# RFID_ver_1_1.net
KiCad netlist of a schematic drawn in EAGLE
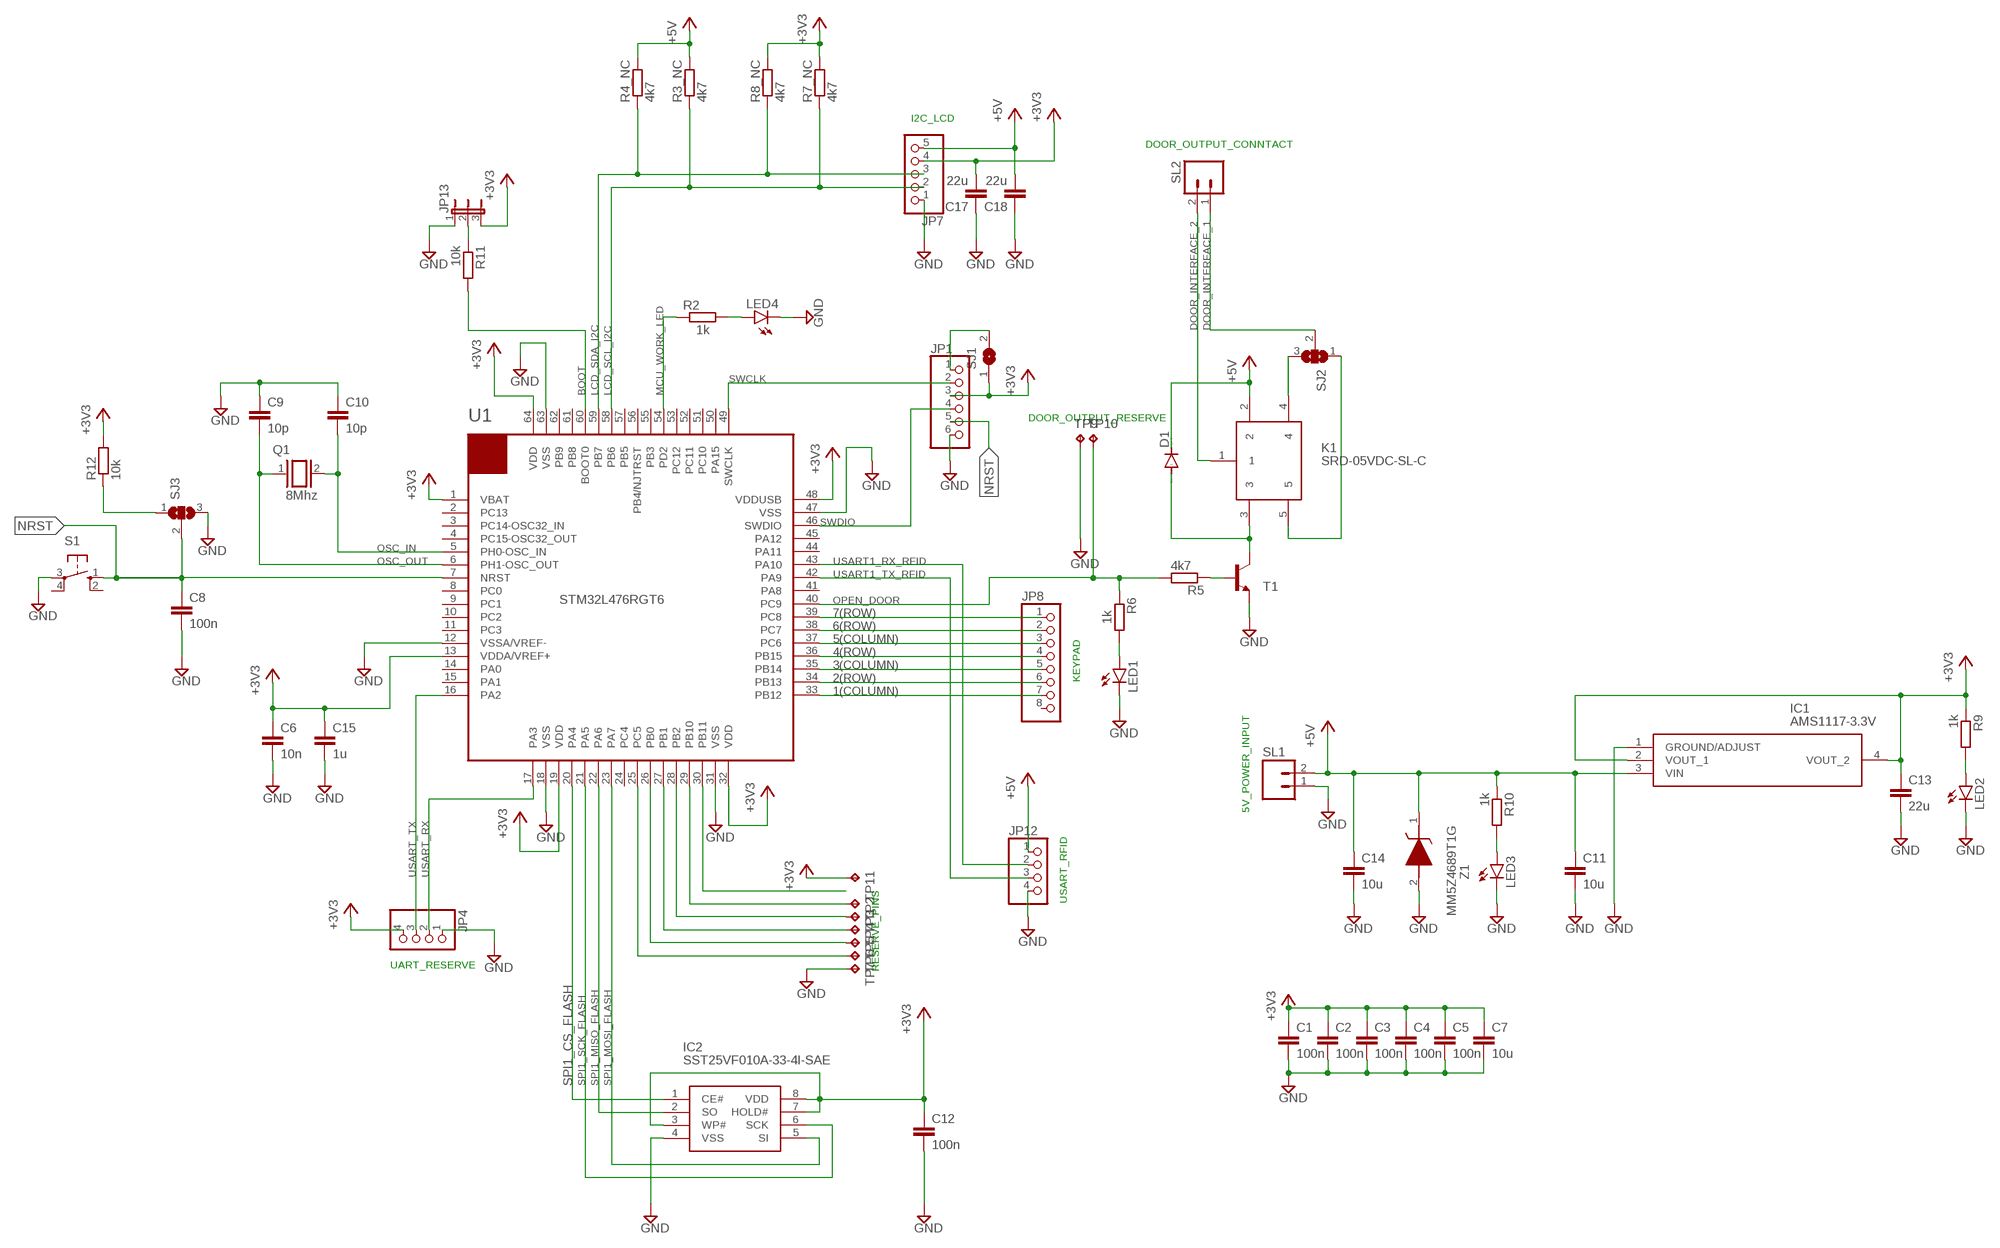
[diagram p0: schematic, sheet 1]

(export (version "E")
  (design (tool "Eeschema 10.0.6"))
  (components
    (comp (ref "C1")
      (value "100n")
      (footprint "eagle-import:C0805")
      (libsource (lib "eagle-import") (part "C-EUC0805"))
    )
    (comp (ref "C2")
      (value "100n")
      (footprint "eagle-import:C0805")
      (libsource (lib "eagle-import") (part "C-EUC0805"))
    )
    (comp (ref "C3")
      (value "100n")
      (footprint "eagle-import:C0805")
      (libsource (lib "eagle-import") (part "C-EUC0805"))
    )
    (comp (ref "C4")
      (value "100n")
      (footprint "eagle-import:C0805")
      (libsource (lib "eagle-import") (part "C-EUC0805"))
    )
    (comp (ref "C5")
      (value "100n")
      (footprint "eagle-import:C0805")
      (libsource (lib "eagle-import") (part "C-EUC0805"))
    )
    (comp (ref "C6")
      (value "10n")
      (footprint "eagle-import:C0805")
      (libsource (lib "eagle-import") (part "C-EUC0805"))
    )
    (comp (ref "C7")
      (value "10u")
      (footprint "eagle-import:C0805")
      (libsource (lib "eagle-import") (part "C-EUC0805"))
    )
    (comp (ref "C8")
      (value "100n")
      (footprint "eagle-import:C0805")
      (libsource (lib "eagle-import") (part "C-EUC0805"))
    )
    (comp (ref "C9")
      (value "10p")
      (footprint "eagle-import:C0805")
      (libsource (lib "eagle-import") (part "C-EUC0805"))
    )
    (comp (ref "C10")
      (value "10p")
      (footprint "eagle-import:C0805")
      (libsource (lib "eagle-import") (part "C-EUC0805"))
    )
    (comp (ref "C11")
      (value "10u")
      (footprint "eagle-import:C0805")
      (libsource (lib "eagle-import") (part "C-EUC0805"))
    )
    (comp (ref "C12")
      (value "100n")
      (footprint "eagle-import:C0805")
      (libsource (lib "eagle-import") (part "C-EUC0805"))
    )
    (comp (ref "C13")
      (value "22u")
      (footprint "eagle-import:C0805")
      (libsource (lib "eagle-import") (part "C-EUC0805"))
    )
    (comp (ref "C14")
      (value "10u")
      (footprint "eagle-import:C0805")
      (libsource (lib "eagle-import") (part "C-EUC0805"))
    )
    (comp (ref "C15")
      (value "1u")
      (footprint "eagle-import:C0805")
      (libsource (lib "eagle-import") (part "C-EUC0805"))
    )
    (comp (ref "C17")
      (value "22u")
      (footprint "eagle-import:C0805")
      (libsource (lib "eagle-import") (part "C-EUC0805"))
    )
    (comp (ref "C18")
      (value "22u")
      (footprint "eagle-import:C0805")
      (libsource (lib "eagle-import") (part "C-EUC0805"))
    )
    (comp (ref "D1")
      (value "DIODE-DO-214AC")
      (footprint "eagle-import:DO-214AC")
      (libsource (lib "eagle-import") (part "DIODE-DO-214AC"))
    )
    (comp (ref "IC1")
      (value "AMS1117-3.3V")
      (footprint "eagle-import:SOT229P700X180-4N")
      (fields (field (name "MANUFACTURER_PART_NUMBER") "ams1117-3.3v"))
      (libsource (lib "eagle-import") (part "AMS1117-3.3V"))
    )
    (comp (ref "IC2")
      (value "SST25VF010A-33-4I-SAE")
      (footprint "eagle-import:SOIC127P600X175-8N")
      (fields (field (name "MOUSER_PART_NUMBER") "804-25VF010A3ISAE"))
      (libsource (lib "eagle-import") (part "SST25VF010A-33-4I-SAE"))
    )
    (comp (ref "JP1")
      (value "PINHD-1X6")
      (footprint "eagle-import:1X06")
      (libsource (lib "eagle-import") (part "PINHD-1X6"))
    )
    (comp (ref "JP4")
      (value "PINHD-1X4")
      (footprint "eagle-import:1X04")
      (libsource (lib "eagle-import") (part "PINHD-1X4"))
    )
    (comp (ref "JP7")
      (value "PINHD-1X5")
      (footprint "eagle-import:1X05")
      (libsource (lib "eagle-import") (part "PINHD-1X5"))
    )
    (comp (ref "JP8")
      (value "PINHD-1X8")
      (footprint "eagle-import:1X08")
      (libsource (lib "eagle-import") (part "PINHD-1X8"))
    )
    (comp (ref "JP12")
      (value "PINHD-1X4")
      (footprint "eagle-import:1X04")
      (libsource (lib "eagle-import") (part "PINHD-1X4"))
    )
    (comp (ref "JP13")
      (value "JP2E")
      (footprint "eagle-import:JP2")
      (libsource (lib "eagle-import") (part "JP2E"))
    )
    (comp (ref "K1")
      (value "SRD-05VDC-SL-C")
      (footprint "eagle-import:SRD")
      (libsource (lib "eagle-import") (part "SRD-05VDC-SL-C"))
    )
    (comp (ref "LED1")
      (value "LEDCHIP-LED0805")
      (footprint "eagle-import:CHIP-LED0805")
      (libsource (lib "eagle-import") (part "LEDCHIP-LED0805"))
    )
    (comp (ref "LED2")
      (value "LEDCHIP-LED0805")
      (footprint "eagle-import:CHIP-LED0805")
      (libsource (lib "eagle-import") (part "LEDCHIP-LED0805"))
    )
    (comp (ref "LED3")
      (value "LEDCHIP-LED0805")
      (footprint "eagle-import:CHIP-LED0805")
      (libsource (lib "eagle-import") (part "LEDCHIP-LED0805"))
    )
    (comp (ref "LED4")
      (value "LEDCHIP-LED0805")
      (footprint "eagle-import:CHIP-LED0805")
      (libsource (lib "eagle-import") (part "LEDCHIP-LED0805"))
    )
    (comp (ref "Q1")
      (value "8Mhz")
      (footprint "eagle-import:QS")
      (libsource (lib "eagle-import") (part "XTAL/S"))
    )
    (comp (ref "R2")
      (value "1k")
      (footprint "eagle-import:R0805")
      (libsource (lib "eagle-import") (part "R-EU_R0805"))
    )
    (comp (ref "R3_NC")
      (value "4k7")
      (footprint "eagle-import:R0805")
      (libsource (lib "eagle-import") (part "R-EU_R0805"))
    )
    (comp (ref "R4_NC")
      (value "4k7")
      (footprint "eagle-import:R0805")
      (libsource (lib "eagle-import") (part "R-EU_R0805"))
    )
    (comp (ref "R5")
      (value "4k7")
      (footprint "eagle-import:R0805")
      (libsource (lib "eagle-import") (part "R-EU_R0805"))
    )
    (comp (ref "R6")
      (value "1k")
      (footprint "eagle-import:R0805")
      (libsource (lib "eagle-import") (part "R-EU_R0805"))
    )
    (comp (ref "R7_NC")
      (value "4k7")
      (footprint "eagle-import:R0805")
      (libsource (lib "eagle-import") (part "R-EU_R0805"))
    )
    (comp (ref "R8_NC")
      (value "4k7")
      (footprint "eagle-import:R0805")
      (libsource (lib "eagle-import") (part "R-EU_R0805"))
    )
    (comp (ref "R9")
      (value "1k")
      (footprint "eagle-import:R0805")
      (libsource (lib "eagle-import") (part "R-EU_R0805"))
    )
    (comp (ref "R10")
      (value "1k")
      (footprint "eagle-import:R0805")
      (libsource (lib "eagle-import") (part "R-EU_R0805"))
    )
    (comp (ref "R11")
      (value "10k")
      (footprint "eagle-import:R0805")
      (libsource (lib "eagle-import") (part "R-EU_R0805"))
    )
    (comp (ref "R12")
      (value "10k")
      (footprint "eagle-import:R0805")
      (libsource (lib "eagle-import") (part "R-EU_R0805"))
    )
    (comp (ref "S1")
      (value "10-XX")
      (footprint "eagle-import:B3F-10XX")
      (fields (field (name "MPN") "B3F-1000"))
      (libsource (lib "eagle-import") (part "10-XX"))
    )
    (comp (ref "SJ1") (value "SJ") (footprint "eagle-import:SJ") (libsource (lib "eagle-import") (part "SJ")))
    (comp (ref "SJ2")
      (value "SJ2W")
      (footprint "eagle-import:SJ_2")
      (libsource (lib "eagle-import") (part "SJ2W"))
    )
    (comp (ref "SJ3")
      (value "SJ2W")
      (footprint "eagle-import:SJ_2")
      (libsource (lib "eagle-import") (part "SJ2W"))
    )
    (comp (ref "SL1")
      (value "M02")
      (footprint "eagle-import:02P")
      (libsource (lib "eagle-import") (part "M02"))
    )
    (comp (ref "SL2")
      (value "M02")
      (footprint "eagle-import:02P")
      (libsource (lib "eagle-import") (part "M02"))
    )
    (comp (ref "T1")
      (value "BC817-NPN-SOT23-BEC")
      (footprint "eagle-import:SOT23-BEC")
      (libsource (lib "eagle-import") (part "-NPN-SOT23-BECBC817"))
    )
    (comp (ref "TP2")
      (value "TPPAD1-13")
      (footprint "eagle-import:P1-13")
      (libsource (lib "eagle-import") (part "TPPAD1-13"))
    )
    (comp (ref "TP3")
      (value "TPPAD1-13")
      (footprint "eagle-import:P1-13")
      (libsource (lib "eagle-import") (part "TPPAD1-13"))
    )
    (comp (ref "TP4")
      (value "TPPAD1-13")
      (footprint "eagle-import:P1-13")
      (libsource (lib "eagle-import") (part "TPPAD1-13"))
    )
    (comp (ref "TP5")
      (value "TPPAD1-13")
      (footprint "eagle-import:P1-13")
      (libsource (lib "eagle-import") (part "TPPAD1-13"))
    )
    (comp (ref "TP6")
      (value "TPPAD1-13")
      (footprint "eagle-import:P1-13")
      (libsource (lib "eagle-import") (part "TPPAD1-13"))
    )
    (comp (ref "TP7")
      (value "TPPAD1-13")
      (footprint "eagle-import:P1-13")
      (libsource (lib "eagle-import") (part "TPPAD1-13"))
    )
    (comp (ref "TP9")
      (value "TPPAD1-17")
      (footprint "eagle-import:P1-17")
      (libsource (lib "eagle-import") (part "TPPAD1-17"))
    )
    (comp (ref "TP10")
      (value "TPPAD1-17")
      (footprint "eagle-import:P1-17")
      (libsource (lib "eagle-import") (part "TPPAD1-17"))
    )
    (comp (ref "TP11")
      (value "TPPAD1-13")
      (footprint "eagle-import:P1-13")
      (libsource (lib "eagle-import") (part "TPPAD1-13"))
    )
    (comp (ref "U1")
      (value "STM32L476RGT6")
      (footprint "eagle-import:LQFP-64")
      (libsource (lib "eagle-import") (part "STM32L476RT6G"))
    )
    (comp (ref "Z1")
      (value "MM5Z4689T1G")
      (footprint "eagle-import:SODFL1608X70N")
      (fields (field (name "MOUSER_PART_NUMBER") "863-MM5Z4689T1G"))
      (libsource (lib "eagle-import") (part "MM5Z4689T1G"))
    )
  )
  (nets
    (net (code "1") (name "+3V3") (class "Default")
      (node (ref "C1") (pin "1") (pinfunction "1_1") (pintype "passive"))
      (node (ref "C12") (pin "1") (pinfunction "1_1") (pintype "passive"))
      (node (ref "C13") (pin "1") (pinfunction "1_1") (pintype "passive"))
      (node (ref "C15") (pin "1") (pinfunction "1_1") (pintype "passive"))
      (node (ref "C17") (pin "2") (pinfunction "2_2") (pintype "passive"))
      (node (ref "C2") (pin "1") (pinfunction "1_1") (pintype "passive"))
      (node (ref "C3") (pin "1") (pinfunction "1_1") (pintype "passive"))
      (node (ref "C4") (pin "1") (pinfunction "1_1") (pintype "passive"))
      (node (ref "C5") (pin "1") (pinfunction "1_1") (pintype "passive"))
      (node (ref "C6") (pin "1") (pinfunction "1_1") (pintype "passive"))
      (node (ref "C7") (pin "1") (pinfunction "1_1") (pintype "passive"))
      (node (ref "IC1") (pin "2") (pinfunction "VOUT_1_2") (pintype "bidirectional"))
      (node (ref "IC1") (pin "4") (pinfunction "VOUT_2_4") (pintype "bidirectional"))
      (node (ref "IC2") (pin "3") (pinfunction "WP#_3") (pintype "bidirectional"))
      (node (ref "IC2") (pin "7") (pinfunction "HOLD#_7") (pintype "bidirectional"))
      (node (ref "IC2") (pin "8") (pinfunction "VDD_8") (pintype "bidirectional"))
      (node (ref "JP1") (pin "3") (pinfunction "3_3") (pintype "passive"))
      (node (ref "JP13") (pin "3") (pinfunction "3_3") (pintype "passive"))
      (node (ref "JP4") (pin "4") (pinfunction "4_4") (pintype "passive"))
      (node (ref "JP7") (pin "4") (pinfunction "4_4") (pintype "passive"))
      (node (ref "R12") (pin "2") (pinfunction "2_2") (pintype "passive"))
      (node (ref "R7_NC") (pin "2") (pinfunction "2_2") (pintype "passive"))
      (node (ref "R8_NC") (pin "2") (pinfunction "2_2") (pintype "passive"))
      (node (ref "R9") (pin "1") (pinfunction "1_1") (pintype "passive"))
      (node (ref "SJ1") (pin "1") (pinfunction "1_1") (pintype "passive"))
      (node (ref "TP11") (pin "TP") (pinfunction "TP_TP") (pintype "input"))
      (node (ref "U1") (pin "1") (pinfunction "VBAT_1") (pintype "power_in"))
      (node (ref "U1") (pin "13") (pinfunction "VDDA/VREF+_13") (pintype "power_in"))
      (node (ref "U1") (pin "19") (pinfunction "VDD_19") (pintype "power_in"))
      (node (ref "U1") (pin "32") (pinfunction "VDD_32") (pintype "power_in"))
      (node (ref "U1") (pin "48") (pinfunction "VDDUSB_48") (pintype "power_in"))
      (node (ref "U1") (pin "64") (pinfunction "VDD_64") (pintype "power_in"))
    )
    (net (code "2") (name "+5V") (class "Default")
      (node (ref "C11") (pin "1") (pinfunction "1_1") (pintype "passive"))
      (node (ref "C14") (pin "1") (pinfunction "1_1") (pintype "passive"))
      (node (ref "C18") (pin "2") (pinfunction "2_2") (pintype "passive"))
      (node (ref "D1") (pin "C") (pinfunction "C_C") (pintype "passive"))
      (node (ref "IC1") (pin "3") (pinfunction "VIN_3") (pintype "bidirectional"))
      (node (ref "JP12") (pin "1") (pinfunction "1_1") (pintype "passive"))
      (node (ref "JP7") (pin "5") (pinfunction "5_5") (pintype "passive"))
      (node (ref "K1") (pin "2") (pinfunction "2_2") (pintype "bidirectional"))
      (node (ref "R10") (pin "1") (pinfunction "1_1") (pintype "passive"))
      (node (ref "R3_NC") (pin "2") (pinfunction "2_2") (pintype "passive"))
      (node (ref "R4_NC") (pin "2") (pinfunction "2_2") (pintype "passive"))
      (node (ref "SL1") (pin "2") (pinfunction "2_2") (pintype "passive"))
      (node (ref "Z1") (pin "1") (pinfunction "K_1") (pintype "bidirectional"))
    )
    (net (code "3") (name "/1(COLUMN)") (class "Default")
      (node (ref "JP8") (pin "7") (pinfunction "7_7") (pintype "passive"))
      (node (ref "U1") (pin "33") (pinfunction "PB12_33") (pintype "bidirectional"))
    )
    (net (code "4") (name "/2(ROW)") (class "Default")
      (node (ref "JP8") (pin "6") (pinfunction "6_6") (pintype "passive"))
      (node (ref "U1") (pin "34") (pinfunction "PB13_34") (pintype "bidirectional"))
    )
    (net (code "5") (name "/3(COLUMN)") (class "Default")
      (node (ref "JP8") (pin "5") (pinfunction "5_5") (pintype "passive"))
      (node (ref "U1") (pin "35") (pinfunction "PB14_35") (pintype "bidirectional"))
    )
    (net (code "6") (name "/4(ROW)") (class "Default")
      (node (ref "JP8") (pin "4") (pinfunction "4_4") (pintype "passive"))
      (node (ref "U1") (pin "36") (pinfunction "PB15_36") (pintype "bidirectional"))
    )
    (net (code "7") (name "/5(COLUMN)") (class "Default")
      (node (ref "JP8") (pin "3") (pinfunction "3_3") (pintype "passive"))
      (node (ref "U1") (pin "37") (pinfunction "PC6_37") (pintype "bidirectional"))
    )
    (net (code "8") (name "/6(ROW)") (class "Default")
      (node (ref "JP8") (pin "2") (pinfunction "2_2") (pintype "passive"))
      (node (ref "U1") (pin "38") (pinfunction "PC7_38") (pintype "bidirectional"))
    )
    (net (code "9") (name "/7(ROW)") (class "Default")
      (node (ref "JP8") (pin "1") (pinfunction "1_1") (pintype "passive"))
      (node (ref "U1") (pin "39") (pinfunction "PC8_39") (pintype "bidirectional"))
    )
    (net (code "10") (name "/BOOT") (class "Default")
      (node (ref "R11") (pin "2") (pinfunction "2_2") (pintype "passive"))
      (node (ref "U1") (pin "60") (pinfunction "BOOT0_60") (pintype "input"))
    )
    (net (code "11") (name "/DOOR_INTERFACE_1") (class "Default")
      (node (ref "SJ2") (pin "2") (pinfunction "2_2") (pintype "passive"))
      (node (ref "SL2") (pin "1") (pinfunction "1_1") (pintype "passive"))
    )
    (net (code "12") (name "/DOOR_INTERFACE_2") (class "Default")
      (node (ref "K1") (pin "1") (pinfunction "1_1") (pintype "bidirectional"))
      (node (ref "SL2") (pin "2") (pinfunction "2_2") (pintype "passive"))
    )
    (net (code "13") (name "/LCD_SCL_I2C") (class "Default")
      (node (ref "JP7") (pin "2") (pinfunction "2_2") (pintype "passive"))
      (node (ref "R3_NC") (pin "1") (pinfunction "1_1") (pintype "passive"))
      (node (ref "R7_NC") (pin "1") (pinfunction "1_1") (pintype "passive"))
      (node (ref "U1") (pin "58") (pinfunction "PB6_58") (pintype "bidirectional"))
    )
    (net (code "14") (name "/LCD_SDA_I2C") (class "Default")
      (node (ref "JP7") (pin "3") (pinfunction "3_3") (pintype "passive"))
      (node (ref "R4_NC") (pin "1") (pinfunction "1_1") (pintype "passive"))
      (node (ref "R8_NC") (pin "1") (pinfunction "1_1") (pintype "passive"))
      (node (ref "U1") (pin "59") (pinfunction "PB7_59") (pintype "bidirectional"))
    )
    (net (code "15") (name "/MCU_WORK_LED") (class "Default")
      (node (ref "R2") (pin "1") (pinfunction "1_1") (pintype "passive"))
      (node (ref "U1") (pin "54") (pinfunction "PD2_54") (pintype "bidirectional"))
    )
    (net (code "16") (name "/OPEN_DOOR") (class "Default")
      (node (ref "R5") (pin "2") (pinfunction "2_2") (pintype "passive"))
      (node (ref "R6") (pin "1") (pinfunction "1_1") (pintype "passive"))
      (node (ref "TP10") (pin "TP") (pinfunction "TP_TP") (pintype "input"))
      (node (ref "U1") (pin "40") (pinfunction "PC9_40") (pintype "bidirectional"))
    )
    (net (code "17") (name "/OSC_IN") (class "Default")
      (node (ref "C10") (pin "2") (pinfunction "2_2") (pintype "passive"))
      (node (ref "Q1") (pin "2") (pinfunction "2_2") (pintype "passive"))
      (node (ref "U1") (pin "5") (pinfunction "PH0-OSC_IN_5") (pintype "bidirectional"))
    )
    (net (code "18") (name "/OSC_OUT") (class "Default")
      (node (ref "C9") (pin "2") (pinfunction "2_2") (pintype "passive"))
      (node (ref "Q1") (pin "1") (pinfunction "1_1") (pintype "passive"))
      (node (ref "U1") (pin "6") (pinfunction "PH1-OSC_OUT_6") (pintype "bidirectional"))
    )
    (net (code "19") (name "/SPI1_CS_FLASH") (class "Default")
      (node (ref "IC2") (pin "1") (pinfunction "CE#_1") (pintype "bidirectional"))
      (node (ref "U1") (pin "20") (pinfunction "PA4_20") (pintype "bidirectional"))
    )
    (net (code "20") (name "/SPI1_MISO_FLASH") (class "Default")
      (node (ref "IC2") (pin "2") (pinfunction "SO_2") (pintype "bidirectional"))
      (node (ref "U1") (pin "22") (pinfunction "PA6_22") (pintype "bidirectional"))
    )
    (net (code "21") (name "/SPI1_MOSI_FLASH") (class "Default")
      (node (ref "IC2") (pin "5") (pinfunction "SI_5") (pintype "bidirectional"))
      (node (ref "U1") (pin "23") (pinfunction "PA7_23") (pintype "bidirectional"))
    )
    (net (code "22") (name "/SPI1_SCK_FLASH") (class "Default")
      (node (ref "IC2") (pin "6") (pinfunction "SCK_6") (pintype "bidirectional"))
      (node (ref "U1") (pin "21") (pinfunction "PA5_21") (pintype "bidirectional"))
    )
    (net (code "23") (name "/SWCLK") (class "Default")
      (node (ref "JP1") (pin "2") (pinfunction "2_2") (pintype "passive"))
      (node (ref "U1") (pin "49") (pinfunction "SWCLK_49") (pintype "bidirectional"))
    )
    (net (code "24") (name "/SWDIO") (class "Default")
      (node (ref "JP1") (pin "4") (pinfunction "4_4") (pintype "passive"))
      (node (ref "U1") (pin "46") (pinfunction "SWDIO_46") (pintype "bidirectional"))
    )
    (net (code "25") (name "/USART1_RX_RFID") (class "Default")
      (node (ref "JP12") (pin "2") (pinfunction "2_2") (pintype "passive"))
      (node (ref "U1") (pin "43") (pinfunction "PA10_43") (pintype "bidirectional"))
    )
    (net (code "26") (name "/USART1_TX_RFID") (class "Default")
      (node (ref "JP12") (pin "3") (pinfunction "3_3") (pintype "passive"))
      (node (ref "U1") (pin "42") (pinfunction "PA9_42") (pintype "bidirectional"))
    )
    (net (code "27") (name "/USART_RX") (class "Default")
      (node (ref "JP4") (pin "2") (pinfunction "2_2") (pintype "passive"))
      (node (ref "U1") (pin "17") (pinfunction "PA3_17") (pintype "bidirectional"))
    )
    (net (code "28") (name "/USART_TX") (class "Default")
      (node (ref "JP4") (pin "3") (pinfunction "3_3") (pintype "passive"))
      (node (ref "U1") (pin "16") (pinfunction "PA2_16") (pintype "bidirectional"))
    )
    (net (code "29") (name "GND") (class "Default")
      (node (ref "C1") (pin "2") (pinfunction "2_2") (pintype "passive"))
      (node (ref "C10") (pin "1") (pinfunction "1_1") (pintype "passive"))
      (node (ref "C11") (pin "2") (pinfunction "2_2") (pintype "passive"))
      (node (ref "C12") (pin "2") (pinfunction "2_2") (pintype "passive"))
      (node (ref "C13") (pin "2") (pinfunction "2_2") (pintype "passive"))
      (node (ref "C14") (pin "2") (pinfunction "2_2") (pintype "passive"))
      (node (ref "C15") (pin "2") (pinfunction "2_2") (pintype "passive"))
      (node (ref "C17") (pin "1") (pinfunction "1_1") (pintype "passive"))
      (node (ref "C18") (pin "1") (pinfunction "1_1") (pintype "passive"))
      (node (ref "C2") (pin "2") (pinfunction "2_2") (pintype "passive"))
      (node (ref "C3") (pin "2") (pinfunction "2_2") (pintype "passive"))
      (node (ref "C4") (pin "2") (pinfunction "2_2") (pintype "passive"))
      (node (ref "C5") (pin "2") (pinfunction "2_2") (pintype "passive"))
      (node (ref "C6") (pin "2") (pinfunction "2_2") (pintype "passive"))
      (node (ref "C7") (pin "2") (pinfunction "2_2") (pintype "passive"))
      (node (ref "C8") (pin "2") (pinfunction "2_2") (pintype "passive"))
      (node (ref "C9") (pin "1") (pinfunction "1_1") (pintype "passive"))
      (node (ref "IC1") (pin "1") (pinfunction "GROUND/ADJUST_1") (pintype "bidirectional"))
      (node (ref "IC2") (pin "4") (pinfunction "VSS_4") (pintype "bidirectional"))
      (node (ref "JP1") (pin "6") (pinfunction "6_6") (pintype "passive"))
      (node (ref "JP12") (pin "4") (pinfunction "4_4") (pintype "passive"))
      (node (ref "JP13") (pin "1") (pinfunction "1_1") (pintype "passive"))
      (node (ref "JP4") (pin "1") (pinfunction "1_1") (pintype "passive"))
      (node (ref "JP7") (pin "1") (pinfunction "1_1") (pintype "passive"))
      (node (ref "LED1") (pin "C") (pinfunction "C_C") (pintype "passive"))
      (node (ref "LED2") (pin "C") (pinfunction "C_C") (pintype "passive"))
      (node (ref "LED3") (pin "C") (pinfunction "C_C") (pintype "passive"))
      (node (ref "LED4") (pin "C") (pinfunction "C_C") (pintype "passive"))
      (node (ref "S1") (pin "3") (pinfunction "P_3") (pintype "passive"))
      (node (ref "SJ3") (pin "3") (pinfunction "3_3") (pintype "passive"))
      (node (ref "SL1") (pin "1") (pinfunction "1_1") (pintype "passive"))
      (node (ref "T1") (pin "E") (pinfunction "E_E") (pintype "passive"))
      (node (ref "TP7") (pin "TP") (pinfunction "TP_TP") (pintype "input"))
      (node (ref "TP9") (pin "TP") (pinfunction "TP_TP") (pintype "input"))
      (node (ref "U1") (pin "12") (pinfunction "VSSA/VREF-_12") (pintype "power_in"))
      (node (ref "U1") (pin "18") (pinfunction "VSS_18") (pintype "power_in"))
      (node (ref "U1") (pin "31") (pinfunction "VSS_31") (pintype "power_in"))
      (node (ref "U1") (pin "47") (pinfunction "VSS_47") (pintype "power_in"))
      (node (ref "U1") (pin "63") (pinfunction "VSS_63") (pintype "power_in"))
      (node (ref "Z1") (pin "2") (pinfunction "A_2") (pintype "bidirectional"))
    )
    (net (code "30") (name "NRST") (class "Default")
      (node (ref "C8") (pin "1") (pinfunction "1_1") (pintype "passive"))
      (node (ref "JP1") (pin "5") (pinfunction "5_5") (pintype "passive"))
      (node (ref "S1") (pin "1") (pinfunction "S_1") (pintype "passive"))
      (node (ref "SJ3") (pin "2") (pinfunction "2_2") (pintype "passive"))
      (node (ref "U1") (pin "7") (pinfunction "NRST_7") (pintype "bidirectional"))
    )
    (net (code "31") (name "Net-(D1-PadA)") (class "Default")
      (node (ref "D1") (pin "A") (pinfunction "A_A") (pintype "passive"))
      (node (ref "K1") (pin "3") (pinfunction "3_3") (pintype "bidirectional"))
      (node (ref "T1") (pin "C") (pinfunction "C_C") (pintype "passive"))
    )
    (net (code "32") (name "Net-(JP1-Pad1)") (class "Default")
      (node (ref "JP1") (pin "1") (pinfunction "1_1") (pintype "passive"))
      (node (ref "SJ1") (pin "2") (pinfunction "2_2") (pintype "passive"))
    )
    (net (code "33") (name "Net-(JP13-Pad2)") (class "Default")
      (node (ref "JP13") (pin "2") (pinfunction "2_2") (pintype "passive"))
      (node (ref "R11") (pin "1") (pinfunction "1_1") (pintype "passive"))
    )
    (net (code "34") (name "Net-(K1-Pad4)") (class "Default")
      (node (ref "K1") (pin "4") (pinfunction "4_4") (pintype "bidirectional"))
      (node (ref "SJ2") (pin "3") (pinfunction "3_3") (pintype "passive"))
    )
    (net (code "35") (name "Net-(K1-Pad5)") (class "Default")
      (node (ref "K1") (pin "5") (pinfunction "5_5") (pintype "bidirectional"))
      (node (ref "SJ2") (pin "1") (pinfunction "1_1") (pintype "passive"))
    )
    (net (code "36") (name "Net-(LED1-PadA)") (class "Default")
      (node (ref "LED1") (pin "A") (pinfunction "A_A") (pintype "passive"))
      (node (ref "R6") (pin "2") (pinfunction "2_2") (pintype "passive"))
    )
    (net (code "37") (name "Net-(LED2-PadA)") (class "Default")
      (node (ref "LED2") (pin "A") (pinfunction "A_A") (pintype "passive"))
      (node (ref "R9") (pin "2") (pinfunction "2_2") (pintype "passive"))
    )
    (net (code "38") (name "Net-(LED3-PadA)") (class "Default")
      (node (ref "LED3") (pin "A") (pinfunction "A_A") (pintype "passive"))
      (node (ref "R10") (pin "2") (pinfunction "2_2") (pintype "passive"))
    )
    (net (code "39") (name "Net-(LED4-PadA)") (class "Default")
      (node (ref "LED4") (pin "A") (pinfunction "A_A") (pintype "passive"))
      (node (ref "R2") (pin "2") (pinfunction "2_2") (pintype "passive"))
    )
    (net (code "40") (name "Net-(R5-Pad1)") (class "Default")
      (node (ref "R5") (pin "1") (pinfunction "1_1") (pintype "passive"))
      (node (ref "T1") (pin "B") (pinfunction "B_B") (pintype "passive"))
    )
    (net (code "41") (name "Net-(R12-Pad1)") (class "Default")
      (node (ref "R12") (pin "1") (pinfunction "1_1") (pintype "passive"))
      (node (ref "SJ3") (pin "1") (pinfunction "1_1") (pintype "passive"))
    )
    (net (code "42") (name "Net-(U1-PB0)") (class "Default")
      (node (ref "TP5") (pin "TP") (pinfunction "TP_TP") (pintype "input"))
      (node (ref "U1") (pin "26") (pinfunction "PB0_26") (pintype "bidirectional"))
    )
    (net (code "43") (name "Net-(U1-PB1)") (class "Default")
      (node (ref "TP4") (pin "TP") (pinfunction "TP_TP") (pintype "input"))
      (node (ref "U1") (pin "27") (pinfunction "PB1_27") (pintype "bidirectional"))
    )
    (net (code "44") (name "Net-(U1-PB2)") (class "Default")
      (node (ref "TP3") (pin "TP") (pinfunction "TP_TP") (pintype "input"))
      (node (ref "U1") (pin "28") (pinfunction "PB2_28") (pintype "bidirectional"))
    )
    (net (code "45") (name "Net-(U1-PB10)") (class "Default")
      (node (ref "TP2") (pin "TP") (pinfunction "TP_TP") (pintype "input"))
      (node (ref "U1") (pin "29") (pinfunction "PB10_29") (pintype "bidirectional"))
    )
    (net (code "46") (name "Net-(U1-PC5)") (class "Default")
      (node (ref "TP6") (pin "TP") (pinfunction "TP_TP") (pintype "input"))
      (node (ref "U1") (pin "25") (pinfunction "PC5_25") (pintype "bidirectional"))
    )
    (net (code "47") (name "unconnected-(JP8-Pad8)") (class "Default")
      (node (ref "JP8") (pin "8") (pinfunction "8_8") (pintype "passive"))
    )
    (net (code "48") (name "unconnected-(S1-P1-Pad4)") (class "Default")
      (node (ref "S1") (pin "4") (pinfunction "P1_4") (pintype "passive"))
    )
    (net (code "49") (name "unconnected-(S1-S1-Pad2)") (class "Default")
      (node (ref "S1") (pin "2") (pinfunction "S1_2") (pintype "passive"))
    )
    (net (code "50") (name "unconnected-(U1-PA0-Pad14)") (class "Default")
      (node (ref "U1") (pin "14") (pinfunction "PA0_14") (pintype "bidirectional"))
    )
    (net (code "51") (name "unconnected-(U1-PA1-Pad15)") (class "Default")
      (node (ref "U1") (pin "15") (pinfunction "PA1_15") (pintype "bidirectional"))
    )
    (net (code "52") (name "unconnected-(U1-PA8-Pad41)") (class "Default")
      (node (ref "U1") (pin "41") (pinfunction "PA8_41") (pintype "bidirectional"))
    )
    (net (code "53") (name "unconnected-(U1-PA11-Pad44)") (class "Default")
      (node (ref "U1") (pin "44") (pinfunction "PA11_44") (pintype "bidirectional"))
    )
    (net (code "54") (name "unconnected-(U1-PA12-Pad45)") (class "Default")
      (node (ref "U1") (pin "45") (pinfunction "PA12_45") (pintype "bidirectional"))
    )
    (net (code "55") (name "unconnected-(U1-PA15-Pad50)") (class "Default")
      (node (ref "U1") (pin "50") (pinfunction "PA15_50") (pintype "bidirectional"))
    )
    (net (code "56") (name "unconnected-(U1-PB3-Pad55)") (class "Default")
      (node (ref "U1") (pin "55") (pinfunction "PB3_55") (pintype "bidirectional"))
    )
    (net (code "57") (name "unconnected-(U1-PB4{slash}NJTRST-Pad56)") (class "Default")
      (node (ref "U1") (pin "56") (pinfunction "PB4/NJTRST_56") (pintype "bidirectional"))
    )
    (net (code "58") (name "unconnected-(U1-PB5-Pad57)") (class "Default")
      (node (ref "U1") (pin "57") (pinfunction "PB5_57") (pintype "bidirectional"))
    )
    (net (code "59") (name "unconnected-(U1-PB8-Pad61)") (class "Default")
      (node (ref "U1") (pin "61") (pinfunction "PB8_61") (pintype "bidirectional"))
    )
    (net (code "60") (name "unconnected-(U1-PB9-Pad62)") (class "Default")
      (node (ref "U1") (pin "62") (pinfunction "PB9_62") (pintype "bidirectional"))
    )
    (net (code "61") (name "unconnected-(U1-PB11-Pad30)") (class "Default")
      (node (ref "U1") (pin "30") (pinfunction "PB11_30") (pintype "bidirectional"))
    )
    (net (code "62") (name "unconnected-(U1-PC0-Pad8)") (class "Default")
      (node (ref "U1") (pin "8") (pinfunction "PC0_8") (pintype "bidirectional"))
    )
    (net (code "63") (name "unconnected-(U1-PC1-Pad9)") (class "Default")
      (node (ref "U1") (pin "9") (pinfunction "PC1_9") (pintype "bidirectional"))
    )
    (net (code "64") (name "unconnected-(U1-PC2-Pad10)") (class "Default")
      (node (ref "U1") (pin "10") (pinfunction "PC2_10") (pintype "bidirectional"))
    )
    (net (code "65") (name "unconnected-(U1-PC3-Pad11)") (class "Default")
      (node (ref "U1") (pin "11") (pinfunction "PC3_11") (pintype "bidirectional"))
    )
    (net (code "66") (name "unconnected-(U1-PC4-Pad24)") (class "Default")
      (node (ref "U1") (pin "24") (pinfunction "PC4_24") (pintype "bidirectional"))
    )
    (net (code "67") (name "unconnected-(U1-PC10-Pad51)") (class "Default")
      (node (ref "U1") (pin "51") (pinfunction "PC10_51") (pintype "bidirectional"))
    )
    (net (code "68") (name "unconnected-(U1-PC11-Pad52)") (class "Default")
      (node (ref "U1") (pin "52") (pinfunction "PC11_52") (pintype "bidirectional"))
    )
    (net (code "69") (name "unconnected-(U1-PC12-Pad53)") (class "Default")
      (node (ref "U1") (pin "53") (pinfunction "PC12_53") (pintype "bidirectional"))
    )
    (net (code "70") (name "unconnected-(U1-PC13-Pad2)") (class "Default")
      (node (ref "U1") (pin "2") (pinfunction "PC13_2") (pintype "bidirectional"))
    )
    (net (code "71") (name "unconnected-(U1-PC14-OSC32_IN-Pad3)") (class "Default")
      (node (ref "U1") (pin "3") (pinfunction "PC14-OSC32_IN_3") (pintype "bidirectional"))
    )
    (net (code "72") (name "unconnected-(U1-PC15-OSC32_OUT-Pad4)") (class "Default")
      (node (ref "U1") (pin "4") (pinfunction "PC15-OSC32_OUT_4") (pintype "bidirectional"))
    )
  )
)
